# NFC_Schematics.net
KiCad netlist of a schematic drawn in Altium Designer
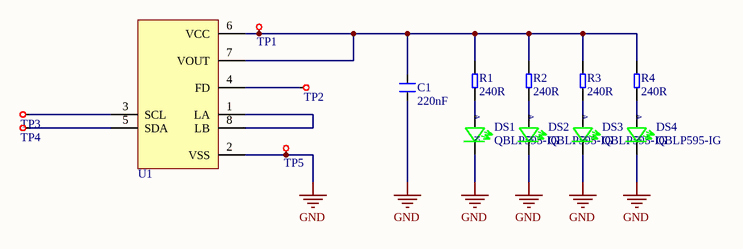
[diagram p0: NFC_Schematics.SchDoc]

(export (version "E")
  (design (tool "Eeschema 10.0.6"))
  (components
    (comp (ref "C1")
      (value "220nF")
      (footprint "CAP_0402")
      (description "0.22µF ±10% 10V Ceramic Capacitor X7R 0402 (1005 Metric)")
      (fields
        (field (name "MANUFACTURER") "Samsung Electro-Mechanics")
        (field (name "MANUFACTURER PART NUMBER") "CL05B224KP5NNNC")
      )
      (libsource (lib "HK_ALTIUM_COM_LIB") (part "CAP_220nF-10V-10%-0402"))
    )
    (comp (ref "DS1")
      (value "QBLP595-IG")
      (footprint "LED_0402")
      (description "LED Uni-Color True Green 2-Pin Chip 0402(1006Metric) T/R")
      (fields (field (name "MANUFACTURER") "QT-Brightek"))
      (libsource (lib "HK_ALTIUM_COM_LIB") (part "LED_Green_0402_3.1V_QBLP595-IG"))
    )
    (comp (ref "DS2")
      (value "QBLP595-IG")
      (footprint "LED_0402")
      (description "LED Uni-Color True Green 2-Pin Chip 0402(1006Metric) T/R")
      (fields (field (name "MANUFACTURER") "QT-Brightek"))
      (libsource (lib "HK_ALTIUM_COM_LIB") (part "LED_Green_0402_3.1V_QBLP595-IG"))
    )
    (comp (ref "DS3")
      (value "QBLP595-IG")
      (footprint "LED_0402")
      (description "LED Uni-Color True Green 2-Pin Chip 0402(1006Metric) T/R")
      (fields (field (name "MANUFACTURER") "QT-Brightek"))
      (libsource (lib "HK_ALTIUM_COM_LIB") (part "LED_Green_0402_3.1V_QBLP595-IG"))
    )
    (comp (ref "DS4")
      (value "QBLP595-IG")
      (footprint "LED_0402")
      (description "LED Uni-Color True Green 2-Pin Chip 0402(1006Metric) T/R")
      (fields (field (name "MANUFACTURER") "QT-Brightek"))
      (libsource (lib "HK_ALTIUM_COM_LIB") (part "LED_Green_0402_3.1V_QBLP595-IG"))
    )
    (comp (ref "R1")
      (value "240R")
      (footprint "RES_0402")
      (description "240 Ohms ±1% 0.1W, 1/10W Chip Resistor 0402 (1005 Metric) Automotive AEC-Q200 Thick Film")
      (fields
        (field (name "MANUFACTURER") "Panasonic Electronic Components")
        (field (name "MANUFACTURER PART NUMBER") "ERJ-2RKF2400X")
      )
      (libsource (lib "HK_ALTIUM_COM_LIB") (part "RES_240R-0.1W-1%-0402"))
    )
    (comp (ref "R2")
      (value "240R")
      (footprint "RES_0402")
      (description "240 Ohms ±1% 0.1W, 1/10W Chip Resistor 0402 (1005 Metric) Automotive AEC-Q200 Thick Film")
      (fields
        (field (name "MANUFACTURER") "Panasonic Electronic Components")
        (field (name "MANUFACTURER PART NUMBER") "ERJ-2RKF2400X")
      )
      (libsource (lib "HK_ALTIUM_COM_LIB") (part "RES_240R-0.1W-1%-0402"))
    )
    (comp (ref "R3")
      (value "240R")
      (footprint "RES_0402")
      (description "240 Ohms ±1% 0.1W, 1/10W Chip Resistor 0402 (1005 Metric) Automotive AEC-Q200 Thick Film")
      (fields
        (field (name "MANUFACTURER") "Panasonic Electronic Components")
        (field (name "MANUFACTURER PART NUMBER") "ERJ-2RKF2400X")
      )
      (libsource (lib "HK_ALTIUM_COM_LIB") (part "RES_240R-0.1W-1%-0402"))
    )
    (comp (ref "R4")
      (value "240R")
      (footprint "RES_0402")
      (description "240 Ohms ±1% 0.1W, 1/10W Chip Resistor 0402 (1005 Metric) Automotive AEC-Q200 Thick Film")
      (fields
        (field (name "MANUFACTURER") "Panasonic Electronic Components")
        (field (name "MANUFACTURER PART NUMBER") "ERJ-2RKF2400X")
      )
      (libsource (lib "HK_ALTIUM_COM_LIB") (part "RES_240R-0.1W-1%-0402"))
    )
    (comp (ref "TP1")
      (value "Test Point SMD Round 0.8mm")
      (footprint "Test Point Round 0.8mm")
      (description "Testpoint SMD Round")
      (libsource (lib "HK_ALTIUM_COM_LIB") (part "Test Point SMD Round 0.8mm"))
    )
    (comp (ref "TP2")
      (value "Test Point SMD Round 0.8mm")
      (footprint "Test Point Round 0.8mm")
      (description "Testpoint SMD Round")
      (libsource (lib "HK_ALTIUM_COM_LIB") (part "Test Point SMD Round 0.8mm"))
    )
    (comp (ref "TP3")
      (value "Test Point SMD Round 0.8mm")
      (footprint "Test Point Round 0.8mm")
      (description "Testpoint SMD Round")
      (libsource (lib "HK_ALTIUM_COM_LIB") (part "Test Point SMD Round 0.8mm"))
    )
    (comp (ref "TP4")
      (value "Test Point SMD Round 0.8mm")
      (footprint "Test Point Round 0.8mm")
      (description "Testpoint SMD Round")
      (libsource (lib "HK_ALTIUM_COM_LIB") (part "Test Point SMD Round 0.8mm"))
    )
    (comp (ref "TP5")
      (value "Test Point SMD Round 0.8mm")
      (footprint "Test Point Round 0.8mm")
      (description "Testpoint SMD Round")
      (libsource (lib "HK_ALTIUM_COM_LIB") (part "Test Point SMD Round 0.8mm"))
    )
    (comp (ref "U1")
      (value "NT3H2111_2211")
      (footprint "IC_NT3H2211W0FHKH")
      (description "RFID Transponder IC 13.56MHz ISO 14443 I²C 3.6V 8-XFQFN Exposed Pad")
      (libsource (lib "HK_ALTIUM_COM_LIB") (part "IC_NFC_"))
    )
  )
  (nets
    (net (code "1") (name "GND") (class "Default")
      (node (ref "C1") (pin "1") (pinfunction "1_1") (pintype "passive"))
      (node (ref "DS1") (pin "2") (pinfunction "2_2") (pintype "passive"))
      (node (ref "DS2") (pin "2") (pinfunction "2_2") (pintype "passive"))
      (node (ref "DS3") (pin "2") (pinfunction "2_2") (pintype "passive"))
      (node (ref "DS4") (pin "2") (pinfunction "2_2") (pintype "passive"))
      (node (ref "TP5") (pin "1") (pinfunction "1_1") (pintype "passive"))
      (node (ref "U1") (pin "2") (pinfunction "VSS_2") (pintype "passive"))
    )
    (net (code "2") (name "Net-(DS1-Pad1)") (class "Default")
      (node (ref "DS1") (pin "1") (pinfunction "1_1") (pintype "passive"))
      (node (ref "R1") (pin "1") (pinfunction "1_1") (pintype "passive"))
    )
    (net (code "3") (name "Net-(DS2-Pad1)") (class "Default")
      (node (ref "DS2") (pin "1") (pinfunction "1_1") (pintype "passive"))
      (node (ref "R2") (pin "1") (pinfunction "1_1") (pintype "passive"))
    )
    (net (code "4") (name "Net-(DS3-Pad1)") (class "Default")
      (node (ref "DS3") (pin "1") (pinfunction "1_1") (pintype "passive"))
      (node (ref "R3") (pin "1") (pinfunction "1_1") (pintype "passive"))
    )
    (net (code "5") (name "Net-(DS4-Pad1)") (class "Default")
      (node (ref "DS4") (pin "1") (pinfunction "1_1") (pintype "passive"))
      (node (ref "R4") (pin "1") (pinfunction "1_1") (pintype "passive"))
    )
    (net (code "6") (name "Net-(U1-FD)") (class "Default")
      (node (ref "TP2") (pin "1") (pinfunction "1_1") (pintype "passive"))
      (node (ref "U1") (pin "4") (pinfunction "FD_4") (pintype "passive"))
    )
    (net (code "7") (name "Net-(U1-LA)") (class "Default")
      (node (ref "U1") (pin "1") (pinfunction "LA_1") (pintype "passive"))
      (node (ref "U1") (pin "8") (pinfunction "LB_8") (pintype "passive"))
    )
    (net (code "8") (name "Net-(U1-SCL)") (class "Default")
      (node (ref "TP3") (pin "1") (pinfunction "1_1") (pintype "passive"))
      (node (ref "U1") (pin "3") (pinfunction "SCL_3") (pintype "passive"))
    )
    (net (code "9") (name "Net-(U1-SDA)") (class "Default")
      (node (ref "TP4") (pin "1") (pinfunction "1_1") (pintype "passive"))
      (node (ref "U1") (pin "5") (pinfunction "SDA_5") (pintype "passive"))
    )
    (net (code "10") (name "Net-(U1-VCC)") (class "Default")
      (node (ref "C1") (pin "2") (pinfunction "2_2") (pintype "passive"))
      (node (ref "R1") (pin "2") (pinfunction "2_2") (pintype "passive"))
      (node (ref "R2") (pin "2") (pinfunction "2_2") (pintype "passive"))
      (node (ref "R3") (pin "2") (pinfunction "2_2") (pintype "passive"))
      (node (ref "R4") (pin "2") (pinfunction "2_2") (pintype "passive"))
      (node (ref "TP1") (pin "1") (pinfunction "1_1") (pintype "passive"))
      (node (ref "U1") (pin "6") (pinfunction "VCC_6") (pintype "passive"))
      (node (ref "U1") (pin "7") (pinfunction "VOUT_7") (pintype "passive"))
    )
  )
)
